# 32u4_Science_Rev_A.net
KiCad netlist of a schematic drawn in EAGLE
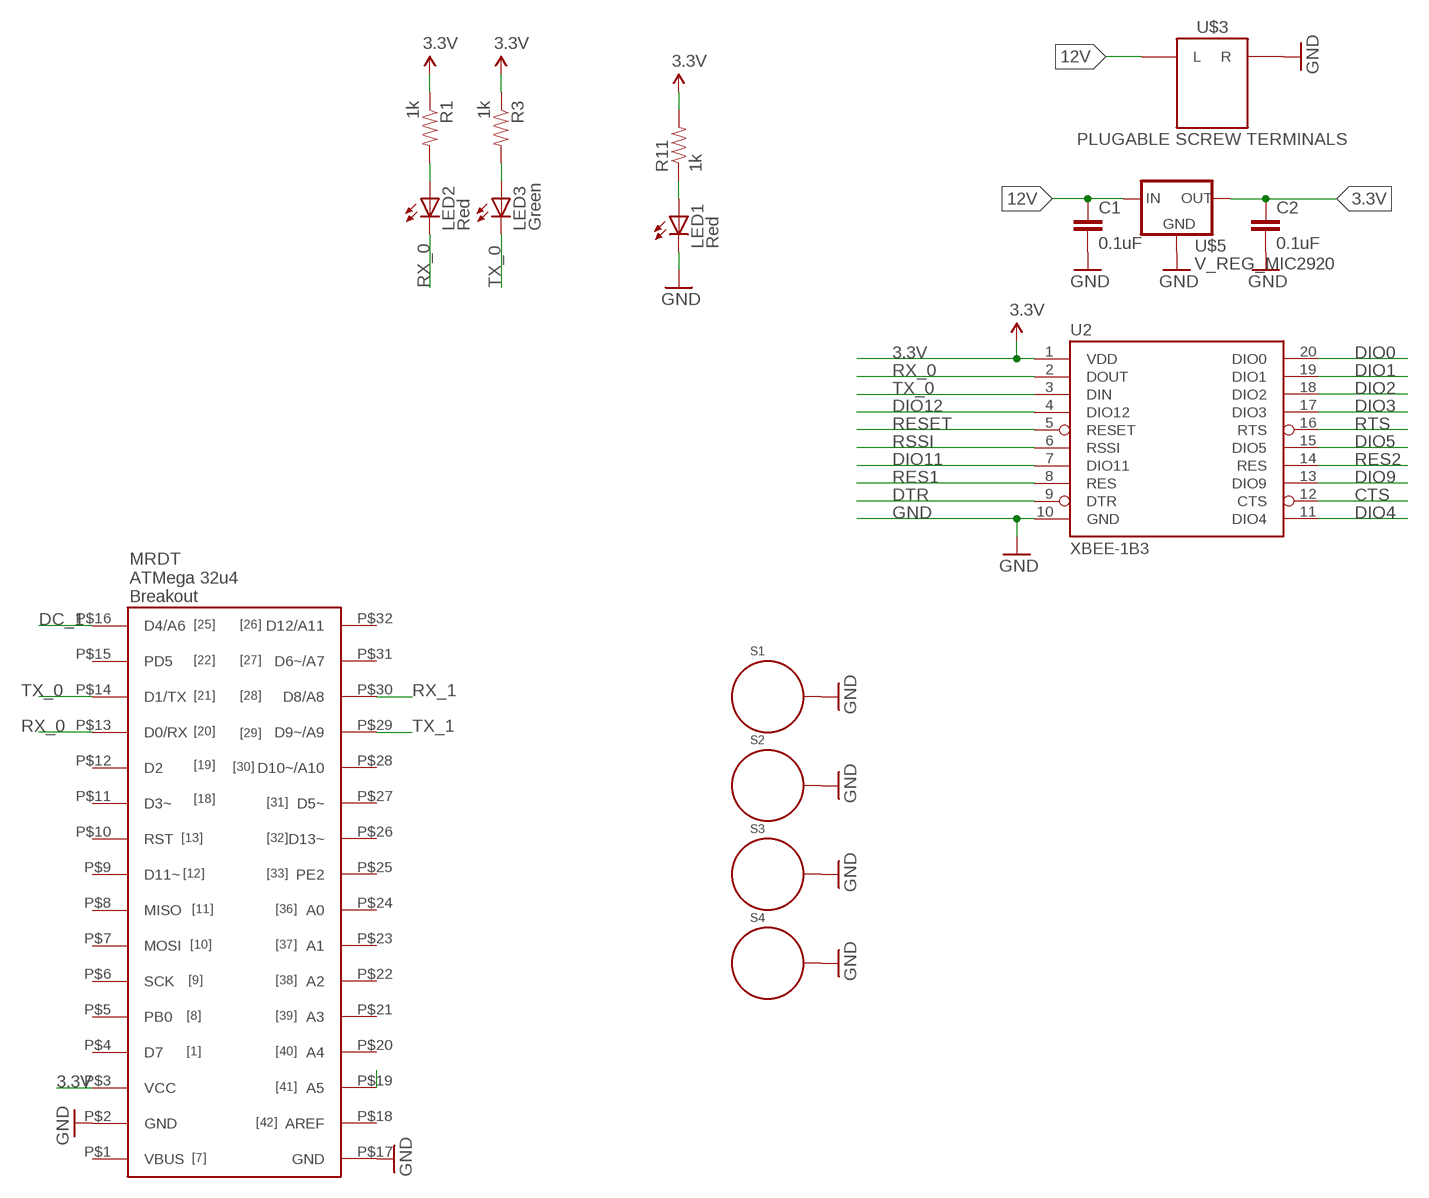
[diagram p0: schematic, sheet 1]

(export (version "E")
  (design (tool "Eeschema 10.0.6"))
  (components
    (comp (ref "C1")
      (value "0.1uF")
      (footprint "eagle-import:1206")
      (libsource (lib "eagle-import") (part "CAP1206"))
    )
    (comp (ref "C2")
      (value "0.1uF")
      (footprint "eagle-import:1206")
      (libsource (lib "eagle-import") (part "CAP1206"))
    )
    (comp (ref "LED1")
      (value "Red")
      (footprint "eagle-import:LED-0603")
      (libsource (lib "eagle-import") (part "LED0603"))
    )
    (comp (ref "LED2")
      (value "Red")
      (footprint "eagle-import:LED-0603")
      (libsource (lib "eagle-import") (part "LED0603"))
    )
    (comp (ref "LED3")
      (value "Green")
      (footprint "eagle-import:LED-0603")
      (libsource (lib "eagle-import") (part "LED0603"))
    )
    (comp (ref "R1")
      (value "1k")
      (footprint "eagle-import:1206")
      (libsource (lib "eagle-import") (part "RESISTOR1206"))
    )
    (comp (ref "R3")
      (value "1k")
      (footprint "eagle-import:1206")
      (libsource (lib "eagle-import") (part "RESISTOR1206"))
    )
    (comp (ref "R11")
      (value "1k")
      (footprint "eagle-import:1206")
      (libsource (lib "eagle-import") (part "RESISTOR1206"))
    )
    (comp (ref "S1")
      (value "STANDOFF_ELECTRICAL")
      (footprint "eagle-import:STANDOFF-ELECTRICAL")
      (libsource (lib "eagle-import") (part "STANDOFF_ELECTRICAL"))
    )
    (comp (ref "S2")
      (value "STANDOFF_ELECTRICAL")
      (footprint "eagle-import:STANDOFF-ELECTRICAL")
      (libsource (lib "eagle-import") (part "STANDOFF_ELECTRICAL"))
    )
    (comp (ref "S3")
      (value "STANDOFF_ELECTRICAL")
      (footprint "eagle-import:STANDOFF-ELECTRICAL")
      (libsource (lib "eagle-import") (part "STANDOFF_ELECTRICAL"))
    )
    (comp (ref "S4")
      (value "STANDOFF_ELECTRICAL")
      (footprint "eagle-import:STANDOFF-ELECTRICAL")
      (libsource (lib "eagle-import") (part "STANDOFF_ELECTRICAL"))
    )
    (comp (ref "U$1")
      (value "32U4_BREAKOU_SMD")
      (footprint "eagle-import:32U3_MCU_DIP_SMD")
      (libsource (lib "eagle-import") (part "32U4_BREAKOU_SMD"))
    )
    (comp (ref "U$3")
      (value "PLUGABLE SCREW TERMINALS")
      (footprint "eagle-import:691321100002")
      (libsource (lib "eagle-import") (part "H_WR-TBL_3210002VERT"))
    )
    (comp (ref "U$5")
      (value "V_REG_MIC2920")
      (footprint "eagle-import:SOT223")
      (libsource (lib "eagle-import") (part "V_REG_MIC2920"))
    )
    (comp (ref "U2")
      (value "XBEE-1B3")
      (footprint "eagle-import:XBEE-SMD")
      (libsource (lib "eagle-import") (part "XBEE-1B3"))
    )
  )
  (nets
    (net (code "1") (name "/CTS") (class "Default")
      (node (ref "U2") (pin "12") (pinfunction "CTS_12") (pintype "output"))
    )
    (net (code "2") (name "/DC_1") (class "Default")
      (node (ref "U$1") (pin "P$16") (pinfunction "D4/A6_P$16") (pintype "bidirectional"))
    )
    (net (code "3") (name "/DIO0") (class "Default")
      (node (ref "U2") (pin "20") (pinfunction "DIO0_20") (pintype "bidirectional"))
    )
    (net (code "4") (name "/DIO1") (class "Default")
      (node (ref "U2") (pin "19") (pinfunction "DIO1_19") (pintype "bidirectional"))
    )
    (net (code "5") (name "/DIO2") (class "Default")
      (node (ref "U2") (pin "18") (pinfunction "DIO2_18") (pintype "bidirectional"))
    )
    (net (code "6") (name "/DIO3") (class "Default")
      (node (ref "U2") (pin "17") (pinfunction "DIO3_17") (pintype "bidirectional"))
    )
    (net (code "7") (name "/DIO4") (class "Default")
      (node (ref "U2") (pin "11") (pinfunction "DIO4_11") (pintype "bidirectional"))
    )
    (net (code "8") (name "/DIO5") (class "Default")
      (node (ref "U2") (pin "15") (pinfunction "DIO5_15") (pintype "bidirectional"))
    )
    (net (code "9") (name "/DIO9") (class "Default")
      (node (ref "U2") (pin "13") (pinfunction "DIO9_13") (pintype "bidirectional"))
    )
    (net (code "10") (name "/DIO11") (class "Default")
      (node (ref "U2") (pin "7") (pinfunction "DIO11_7") (pintype "bidirectional"))
    )
    (net (code "11") (name "/DIO12") (class "Default")
      (node (ref "U2") (pin "4") (pinfunction "DIO12_4") (pintype "bidirectional"))
    )
    (net (code "12") (name "/DTR") (class "Default")
      (node (ref "U2") (pin "9") (pinfunction "DTR_9") (pintype "bidirectional"))
    )
    (net (code "13") (name "/RES1") (class "Default")
      (node (ref "U2") (pin "8") (pinfunction "RES_8") (pintype "bidirectional"))
    )
    (net (code "14") (name "/RES2") (class "Default")
      (node (ref "U2") (pin "14") (pinfunction "RES_14") (pintype "bidirectional"))
    )
    (net (code "15") (name "/RESET") (class "Default")
      (node (ref "U2") (pin "5") (pinfunction "RESET_5") (pintype "input"))
    )
    (net (code "16") (name "/RSSI") (class "Default")
      (node (ref "U2") (pin "6") (pinfunction "RSSI_6") (pintype "bidirectional"))
    )
    (net (code "17") (name "/RTS") (class "Default")
      (node (ref "U2") (pin "16") (pinfunction "RTS_16") (pintype "input"))
    )
    (net (code "18") (name "/RX_0") (class "Default")
      (node (ref "LED2") (pin "C") (pinfunction "C_C") (pintype "passive"))
      (node (ref "U$1") (pin "P$13") (pinfunction "D0/RX_P$13") (pintype "bidirectional"))
      (node (ref "U2") (pin "2") (pinfunction "DOUT_2") (pintype "output"))
    )
    (net (code "19") (name "/RX_1") (class "Default")
      (node (ref "U$1") (pin "P$30") (pinfunction "D8/A8_P$30") (pintype "bidirectional"))
    )
    (net (code "20") (name "/TX_0") (class "Default")
      (node (ref "LED3") (pin "C") (pinfunction "C_C") (pintype "passive"))
      (node (ref "U$1") (pin "P$14") (pinfunction "D1/TX_P$14") (pintype "bidirectional"))
      (node (ref "U2") (pin "3") (pinfunction "DIN_3") (pintype "input"))
    )
    (net (code "21") (name "/TX_1") (class "Default")
      (node (ref "U$1") (pin "P$29") (pinfunction "D9~{/A9}_P$29") (pintype "bidirectional"))
    )
    (net (code "22") (name "3.3V") (class "Default")
      (node (ref "C2") (pin "1") (pinfunction "1_1") (pintype "passive"))
      (node (ref "R1") (pin "1") (pinfunction "1_1") (pintype "passive"))
      (node (ref "R11") (pin "2") (pinfunction "2_2") (pintype "passive"))
      (node (ref "R3") (pin "1") (pinfunction "1_1") (pintype "passive"))
      (node (ref "U$1") (pin "P$3") (pinfunction "VCC_P$3") (pintype "bidirectional"))
      (node (ref "U$5") (pin "3") (pinfunction "OUT_3") (pintype "output"))
      (node (ref "U2") (pin "1") (pinfunction "VDD_1") (pintype "power_in"))
    )
    (net (code "23") (name "12V") (class "Default")
      (node (ref "C1") (pin "1") (pinfunction "1_1") (pintype "passive"))
      (node (ref "U$3") (pin "L") (pinfunction "L_L") (pintype "bidirectional"))
      (node (ref "U$5") (pin "1") (pinfunction "IN_1") (pintype "input"))
    )
    (net (code "24") (name "GND") (class "Default")
      (node (ref "C1") (pin "2") (pinfunction "2_2") (pintype "passive"))
      (node (ref "C2") (pin "2") (pinfunction "2_2") (pintype "passive"))
      (node (ref "LED1") (pin "C") (pinfunction "C_C") (pintype "passive"))
      (node (ref "S1") (pin "P1") (pinfunction "P$1_P1") (pintype "bidirectional"))
      (node (ref "S2") (pin "P1") (pinfunction "P$1_P1") (pintype "bidirectional"))
      (node (ref "S3") (pin "P1") (pinfunction "P$1_P1") (pintype "bidirectional"))
      (node (ref "S4") (pin "P1") (pinfunction "P$1_P1") (pintype "bidirectional"))
      (node (ref "U$1") (pin "P$17") (pinfunction "GND_P$17") (pintype "bidirectional"))
      (node (ref "U$1") (pin "P$2") (pinfunction "GND_P$2") (pintype "bidirectional"))
      (node (ref "U$3") (pin "R") (pinfunction "R_R") (pintype "bidirectional"))
      (node (ref "U$5") (pin "2") (pinfunction "GND_2") (pintype "input"))
      (node (ref "U$5") (pin "4") (pinfunction "GND_4") (pintype "input"))
      (node (ref "U2") (pin "10") (pinfunction "GND_10") (pintype "power_in"))
    )
    (net (code "25") (name "Net-(LED1-PadA)") (class "Default")
      (node (ref "LED1") (pin "A") (pinfunction "A_A") (pintype "passive"))
      (node (ref "R11") (pin "1") (pinfunction "1_1") (pintype "passive"))
    )
    (net (code "26") (name "Net-(LED2-PadA)") (class "Default")
      (node (ref "LED2") (pin "A") (pinfunction "A_A") (pintype "passive"))
      (node (ref "R1") (pin "2") (pinfunction "2_2") (pintype "passive"))
    )
    (net (code "27") (name "Net-(LED3-PadA)") (class "Default")
      (node (ref "LED3") (pin "A") (pinfunction "A_A") (pintype "passive"))
      (node (ref "R3") (pin "2") (pinfunction "2_2") (pintype "passive"))
    )
    (net (code "28") (name "unconnected-(U$1-A0-PadP$24)") (class "Default")
      (node (ref "U$1") (pin "P$24") (pinfunction "A0_P$24") (pintype "bidirectional"))
    )
    (net (code "29") (name "unconnected-(U$1-A1-PadP$23)") (class "Default")
      (node (ref "U$1") (pin "P$23") (pinfunction "A1_P$23") (pintype "bidirectional"))
    )
    (net (code "30") (name "unconnected-(U$1-A2-PadP$22)") (class "Default")
      (node (ref "U$1") (pin "P$22") (pinfunction "A2_P$22") (pintype "bidirectional"))
    )
    (net (code "31") (name "unconnected-(U$1-A3-PadP$21)") (class "Default")
      (node (ref "U$1") (pin "P$21") (pinfunction "A3_P$21") (pintype "bidirectional"))
    )
    (net (code "32") (name "unconnected-(U$1-A4-PadP$20)") (class "Default")
      (node (ref "U$1") (pin "P$20") (pinfunction "A4_P$20") (pintype "bidirectional"))
    )
    (net (code "33") (name "unconnected-(U$1-A5-PadP$19)") (class "Default")
      (node (ref "U$1") (pin "P$19") (pinfunction "A5_P$19") (pintype "bidirectional"))
    )
    (net (code "34") (name "unconnected-(U$1-AREF-PadP$18)") (class "Default")
      (node (ref "U$1") (pin "P$18") (pinfunction "AREF_P$18") (pintype "bidirectional"))
    )
    (net (code "35") (name "unconnected-(U$1-D2-PadP$12)") (class "Default")
      (node (ref "U$1") (pin "P$12") (pinfunction "D2_P$12") (pintype "bidirectional"))
    )
    (net (code "36") (name "unconnected-(U$1-D3~{}-PadP$11)") (class "Default")
      (node (ref "U$1") (pin "P$11") (pinfunction "D3~{}_P$11") (pintype "bidirectional"))
    )
    (net (code "37") (name "unconnected-(U$1-D5~{}-PadP$27)") (class "Default")
      (node (ref "U$1") (pin "P$27") (pinfunction "D5~{}_P$27") (pintype "bidirectional"))
    )
    (net (code "38") (name "unconnected-(U$1-D6~{{slash}A7}-PadP$31)") (class "Default")
      (node (ref "U$1") (pin "P$31") (pinfunction "D6~{/A7}_P$31") (pintype "bidirectional"))
    )
    (net (code "39") (name "unconnected-(U$1-D7-PadP$4)") (class "Default")
      (node (ref "U$1") (pin "P$4") (pinfunction "D7_P$4") (pintype "bidirectional"))
    )
    (net (code "40") (name "unconnected-(U$1-D10~{{slash}A10}-PadP$28)") (class "Default")
      (node (ref "U$1") (pin "P$28") (pinfunction "D10~{/A10}_P$28") (pintype "bidirectional"))
    )
    (net (code "41") (name "unconnected-(U$1-D11~{}-PadP$9)") (class "Default")
      (node (ref "U$1") (pin "P$9") (pinfunction "D11~{}_P$9") (pintype "bidirectional"))
    )
    (net (code "42") (name "unconnected-(U$1-D12{slash}A11-PadP$32)") (class "Default")
      (node (ref "U$1") (pin "P$32") (pinfunction "D12/A11_P$32") (pintype "bidirectional"))
    )
    (net (code "43") (name "unconnected-(U$1-D13~{}-PadP$26)") (class "Default")
      (node (ref "U$1") (pin "P$26") (pinfunction "D13~{}_P$26") (pintype "bidirectional"))
    )
    (net (code "44") (name "unconnected-(U$1-MISO-PadP$8)") (class "Default")
      (node (ref "U$1") (pin "P$8") (pinfunction "MISO_P$8") (pintype "bidirectional"))
    )
    (net (code "45") (name "unconnected-(U$1-MOSI-PadP$7)") (class "Default")
      (node (ref "U$1") (pin "P$7") (pinfunction "MOSI_P$7") (pintype "bidirectional"))
    )
    (net (code "46") (name "unconnected-(U$1-PB0-PadP$5)") (class "Default")
      (node (ref "U$1") (pin "P$5") (pinfunction "PB0_P$5") (pintype "bidirectional"))
    )
    (net (code "47") (name "unconnected-(U$1-PD5-PadP$15)") (class "Default")
      (node (ref "U$1") (pin "P$15") (pinfunction "PD5_P$15") (pintype "bidirectional"))
    )
    (net (code "48") (name "unconnected-(U$1-PE2-PadP$25)") (class "Default")
      (node (ref "U$1") (pin "P$25") (pinfunction "PE2_P$25") (pintype "bidirectional"))
    )
    (net (code "49") (name "unconnected-(U$1-RST-PadP$10)") (class "Default")
      (node (ref "U$1") (pin "P$10") (pinfunction "RST_P$10") (pintype "bidirectional"))
    )
    (net (code "50") (name "unconnected-(U$1-SCK-PadP$6)") (class "Default")
      (node (ref "U$1") (pin "P$6") (pinfunction "SCK_P$6") (pintype "bidirectional"))
    )
    (net (code "51") (name "unconnected-(U$1-VBUS-PadP$1)") (class "Default")
      (node (ref "U$1") (pin "P$1") (pinfunction "VBUS_P$1") (pintype "bidirectional"))
    )
  )
)
